# GOTEK_Speaker_Circuit_-_On_Board.net
KiCad netlist of a schematic drawn in EAGLE
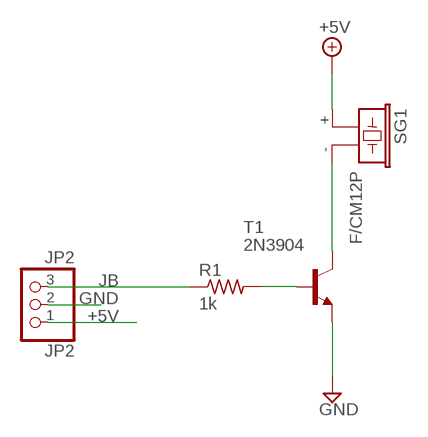
[diagram p0: schematic, sheet 1]

(export (version "E")
  (design (tool "Eeschema 10.0.6"))
  (components
    (comp (ref "JP2")
      (value "JP2")
      (footprint "eagle-import:1X03")
      (libsource (lib "eagle-import") (part "PINHD-1X3"))
    )
    (comp (ref "R1")
      (value "1k")
      (footprint "eagle-import:0204_7")
      (libsource (lib "eagle-import") (part "R-US_0204/7"))
    )
    (comp (ref "SG1")
      (value "F/CM12P")
      (footprint "eagle-import:F_CM12P")
      (libsource (lib "eagle-import") (part "F/CM12P"))
    )
    (comp (ref "T1")
      (value "2N3904")
      (footprint "eagle-import:TO92")
      (libsource (lib "eagle-import") (part "2N3904"))
    )
  )
  (nets
    (net (code "1") (name "+5V") (class "Default")
      (node (ref "JP2") (pin "1") (pinfunction "1_1") (pintype "passive"))
      (node (ref "SG1") (pin "+") (pinfunction "1_+") (pintype "passive"))
    )
    (net (code "2") (name "/JB") (class "Default")
      (node (ref "JP2") (pin "3") (pinfunction "3_3") (pintype "passive"))
      (node (ref "R1") (pin "1") (pinfunction "1_1") (pintype "passive"))
    )
    (net (code "3") (name "GND") (class "Default")
      (node (ref "JP2") (pin "2") (pinfunction "2_2") (pintype "passive"))
      (node (ref "T1") (pin "3") (pinfunction "E_3") (pintype "passive"))
    )
    (net (code "4") (name "Net-(SG1-2)") (class "Default")
      (node (ref "SG1") (pin "-") (pinfunction "2_-") (pintype "passive"))
      (node (ref "T1") (pin "1") (pinfunction "C_1") (pintype "passive"))
    )
    (net (code "5") (name "Net-(T1-B)") (class "Default")
      (node (ref "R1") (pin "2") (pinfunction "2_2") (pintype "passive"))
      (node (ref "T1") (pin "2") (pinfunction "B_2") (pintype "passive"))
    )
  )
)
